# S7CAS-PLEIADES-CARTE-MERE_P06_FLASH.net
KiCad netlist of a schematic drawn in Altium Designer
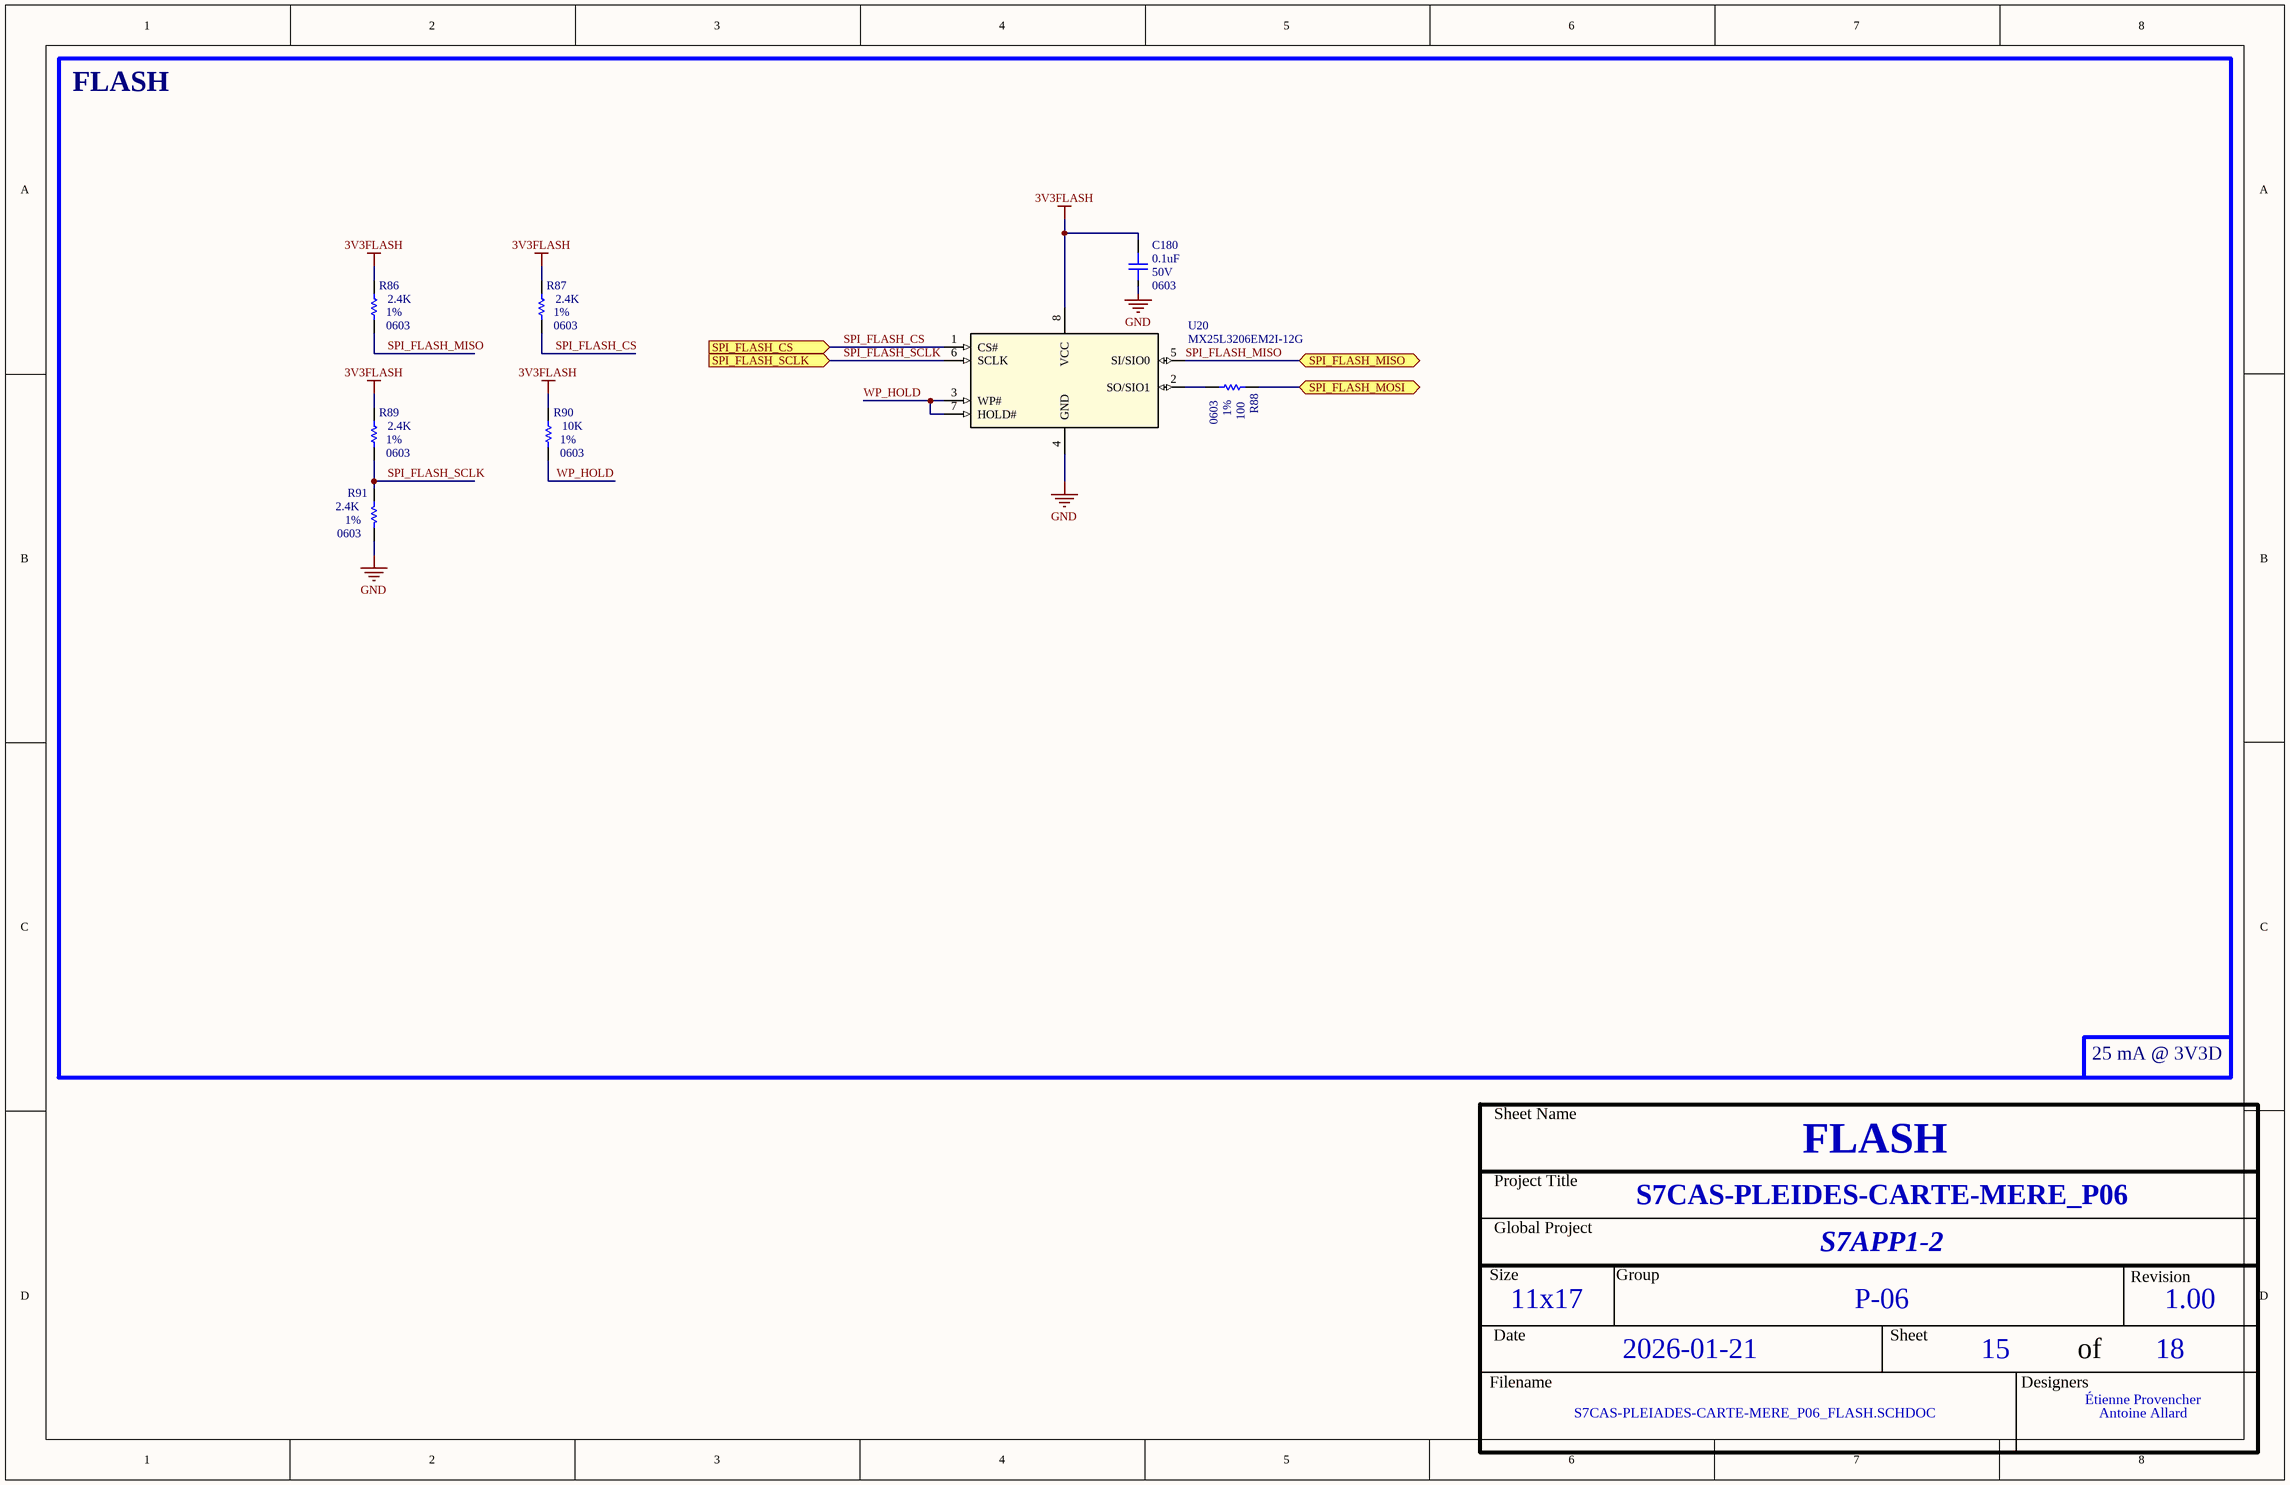
[diagram p0: S7CAS-PLEIADES-CARTE-MERE_P06_FLASH.SCHDOC]

(export (version "E")
  (design (tool "Eeschema 10.0.6"))
  (components
    (comp (ref "C180")
      (value "0.1uF")
      (footprint "CAP_0603")
      (description "CAP - 0603")
      (fields
        (field (name "VOLTAGE") "50V")
        (field (name "PACKAGE") "0603")
        (field (name "CREATEDBY") "Jonathan Bouchard")
      )
      (libsource (lib "s7cas_lib2023") (part "CAP - 0603"))
    )
    (comp (ref "R86")
      (value "2.4K")
      (footprint "RES_0603")
      (description "RES - 0603")
      (fields
        (field (name "PACKAGE") "0603")
        (field (name "PRECISION") "1%")
        (field (name "CREATEDBY") "Jonathan Bouchard")
      )
      (libsource (lib "s7cas_lib2023") (part "RES - 0603"))
    )
    (comp (ref "R87")
      (value "2.4K")
      (footprint "RES_0603")
      (description "RES - 0603")
      (fields
        (field (name "PACKAGE") "0603")
        (field (name "PRECISION") "1%")
        (field (name "CREATEDBY") "Jonathan Bouchard")
      )
      (libsource (lib "s7cas_lib2023") (part "RES - 0603"))
    )
    (comp (ref "R88")
      (value "100")
      (footprint "RES_0603")
      (description "RES - 0603")
      (fields
        (field (name "PACKAGE") "0603")
        (field (name "PRECISION") "1%")
        (field (name "CREATEDBY") "Jonathan Bouchard")
      )
      (libsource (lib "s7cas_lib2023") (part "RES - 0603"))
    )
    (comp (ref "R89")
      (value "2.4K")
      (footprint "RES_0603")
      (description "RES - 0603")
      (fields
        (field (name "PACKAGE") "0603")
        (field (name "PRECISION") "1%")
        (field (name "CREATEDBY") "Jonathan Bouchard")
      )
      (libsource (lib "s7cas_lib2023") (part "RES - 0603"))
    )
    (comp (ref "R90")
      (value "10K")
      (footprint "RES_0603")
      (description "RES - 0603")
      (fields
        (field (name "PACKAGE") "0603")
        (field (name "PRECISION") "1%")
        (field (name "CREATEDBY") "Jonathan Bouchard")
      )
      (libsource (lib "s7cas_lib2023") (part "RES - 0603"))
    )
    (comp (ref "R91")
      (value "2.4K")
      (footprint "RES_0603")
      (description "RES - 0603")
      (fields
        (field (name "PACKAGE") "0603")
        (field (name "PRECISION") "1%")
        (field (name "CREATEDBY") "Jonathan Bouchard")
      )
      (libsource (lib "s7cas_lib2023") (part "RES - 0603"))
    )
    (comp (ref "U20")
      (value "MX25L3206EM2I-12G")
      (footprint "SOP8L_200MIL_6110-1406_MAC")
      (description "Description")
      (fields (field (name "COPYRIGHT") "Copyright (C) 2025 Ultra Librarian. All rights reserved."))
      (libsource (lib "MX25L3206EM2I-12G") (part "MX25L3206EM2I-12G"))
    )
  )
  (nets
    (net (code "1") (name "/SPI_FLASH_CS") (class "Default")
      (node (ref "R87") (pin "1") (pinfunction "1_1") (pintype "passive"))
      (node (ref "U20") (pin "1") (pinfunction "CS#_1") (pintype "input"))
    )
    (net (code "2") (name "/SPI_FLASH_MISO") (class "Default")
      (node (ref "R86") (pin "1") (pinfunction "1_1") (pintype "passive"))
      (node (ref "U20") (pin "5") (pinfunction "SI/SIO0_5") (pintype "bidirectional"))
    )
    (net (code "3") (name "/SPI_FLASH_MOSI") (class "Default")
      (node (ref "R88") (pin "2") (pinfunction "2_2") (pintype "passive"))
    )
    (net (code "4") (name "/SPI_FLASH_SCLK") (class "Default")
      (node (ref "R89") (pin "1") (pinfunction "1_1") (pintype "passive"))
      (node (ref "R91") (pin "2") (pinfunction "2_2") (pintype "passive"))
      (node (ref "U20") (pin "6") (pinfunction "SCLK_6") (pintype "input"))
    )
    (net (code "5") (name "/WP_HOLD") (class "Default")
      (node (ref "R90") (pin "1") (pinfunction "1_1") (pintype "passive"))
      (node (ref "U20") (pin "3") (pinfunction "WP#_3") (pintype "input"))
      (node (ref "U20") (pin "7") (pinfunction "HOLD#_7") (pintype "input"))
    )
    (net (code "6") (name "3V3FLASH") (class "Default")
      (node (ref "C180") (pin "2") (pinfunction "2_2") (pintype "passive"))
      (node (ref "R86") (pin "2") (pinfunction "2_2") (pintype "passive"))
      (node (ref "R87") (pin "2") (pinfunction "2_2") (pintype "passive"))
      (node (ref "R89") (pin "2") (pinfunction "2_2") (pintype "passive"))
      (node (ref "R90") (pin "2") (pinfunction "2_2") (pintype "passive"))
      (node (ref "U20") (pin "8") (pinfunction "VCC_8") (pintype "power_in"))
    )
    (net (code "7") (name "GND") (class "Default")
      (node (ref "C180") (pin "1") (pinfunction "1_1") (pintype "passive"))
      (node (ref "R91") (pin "1") (pinfunction "1_1") (pintype "passive"))
      (node (ref "U20") (pin "4") (pinfunction "GND_4") (pintype "power_in"))
    )
    (net (code "8") (name "Net-(U20-SO{slash}SIO1)") (class "Default")
      (node (ref "R88") (pin "1") (pinfunction "1_1") (pintype "passive"))
      (node (ref "U20") (pin "2") (pinfunction "SO/SIO1_2") (pintype "bidirectional"))
    )
  )
)
